# MOSFETS.net
KiCad netlist of a schematic drawn in Altium Designer
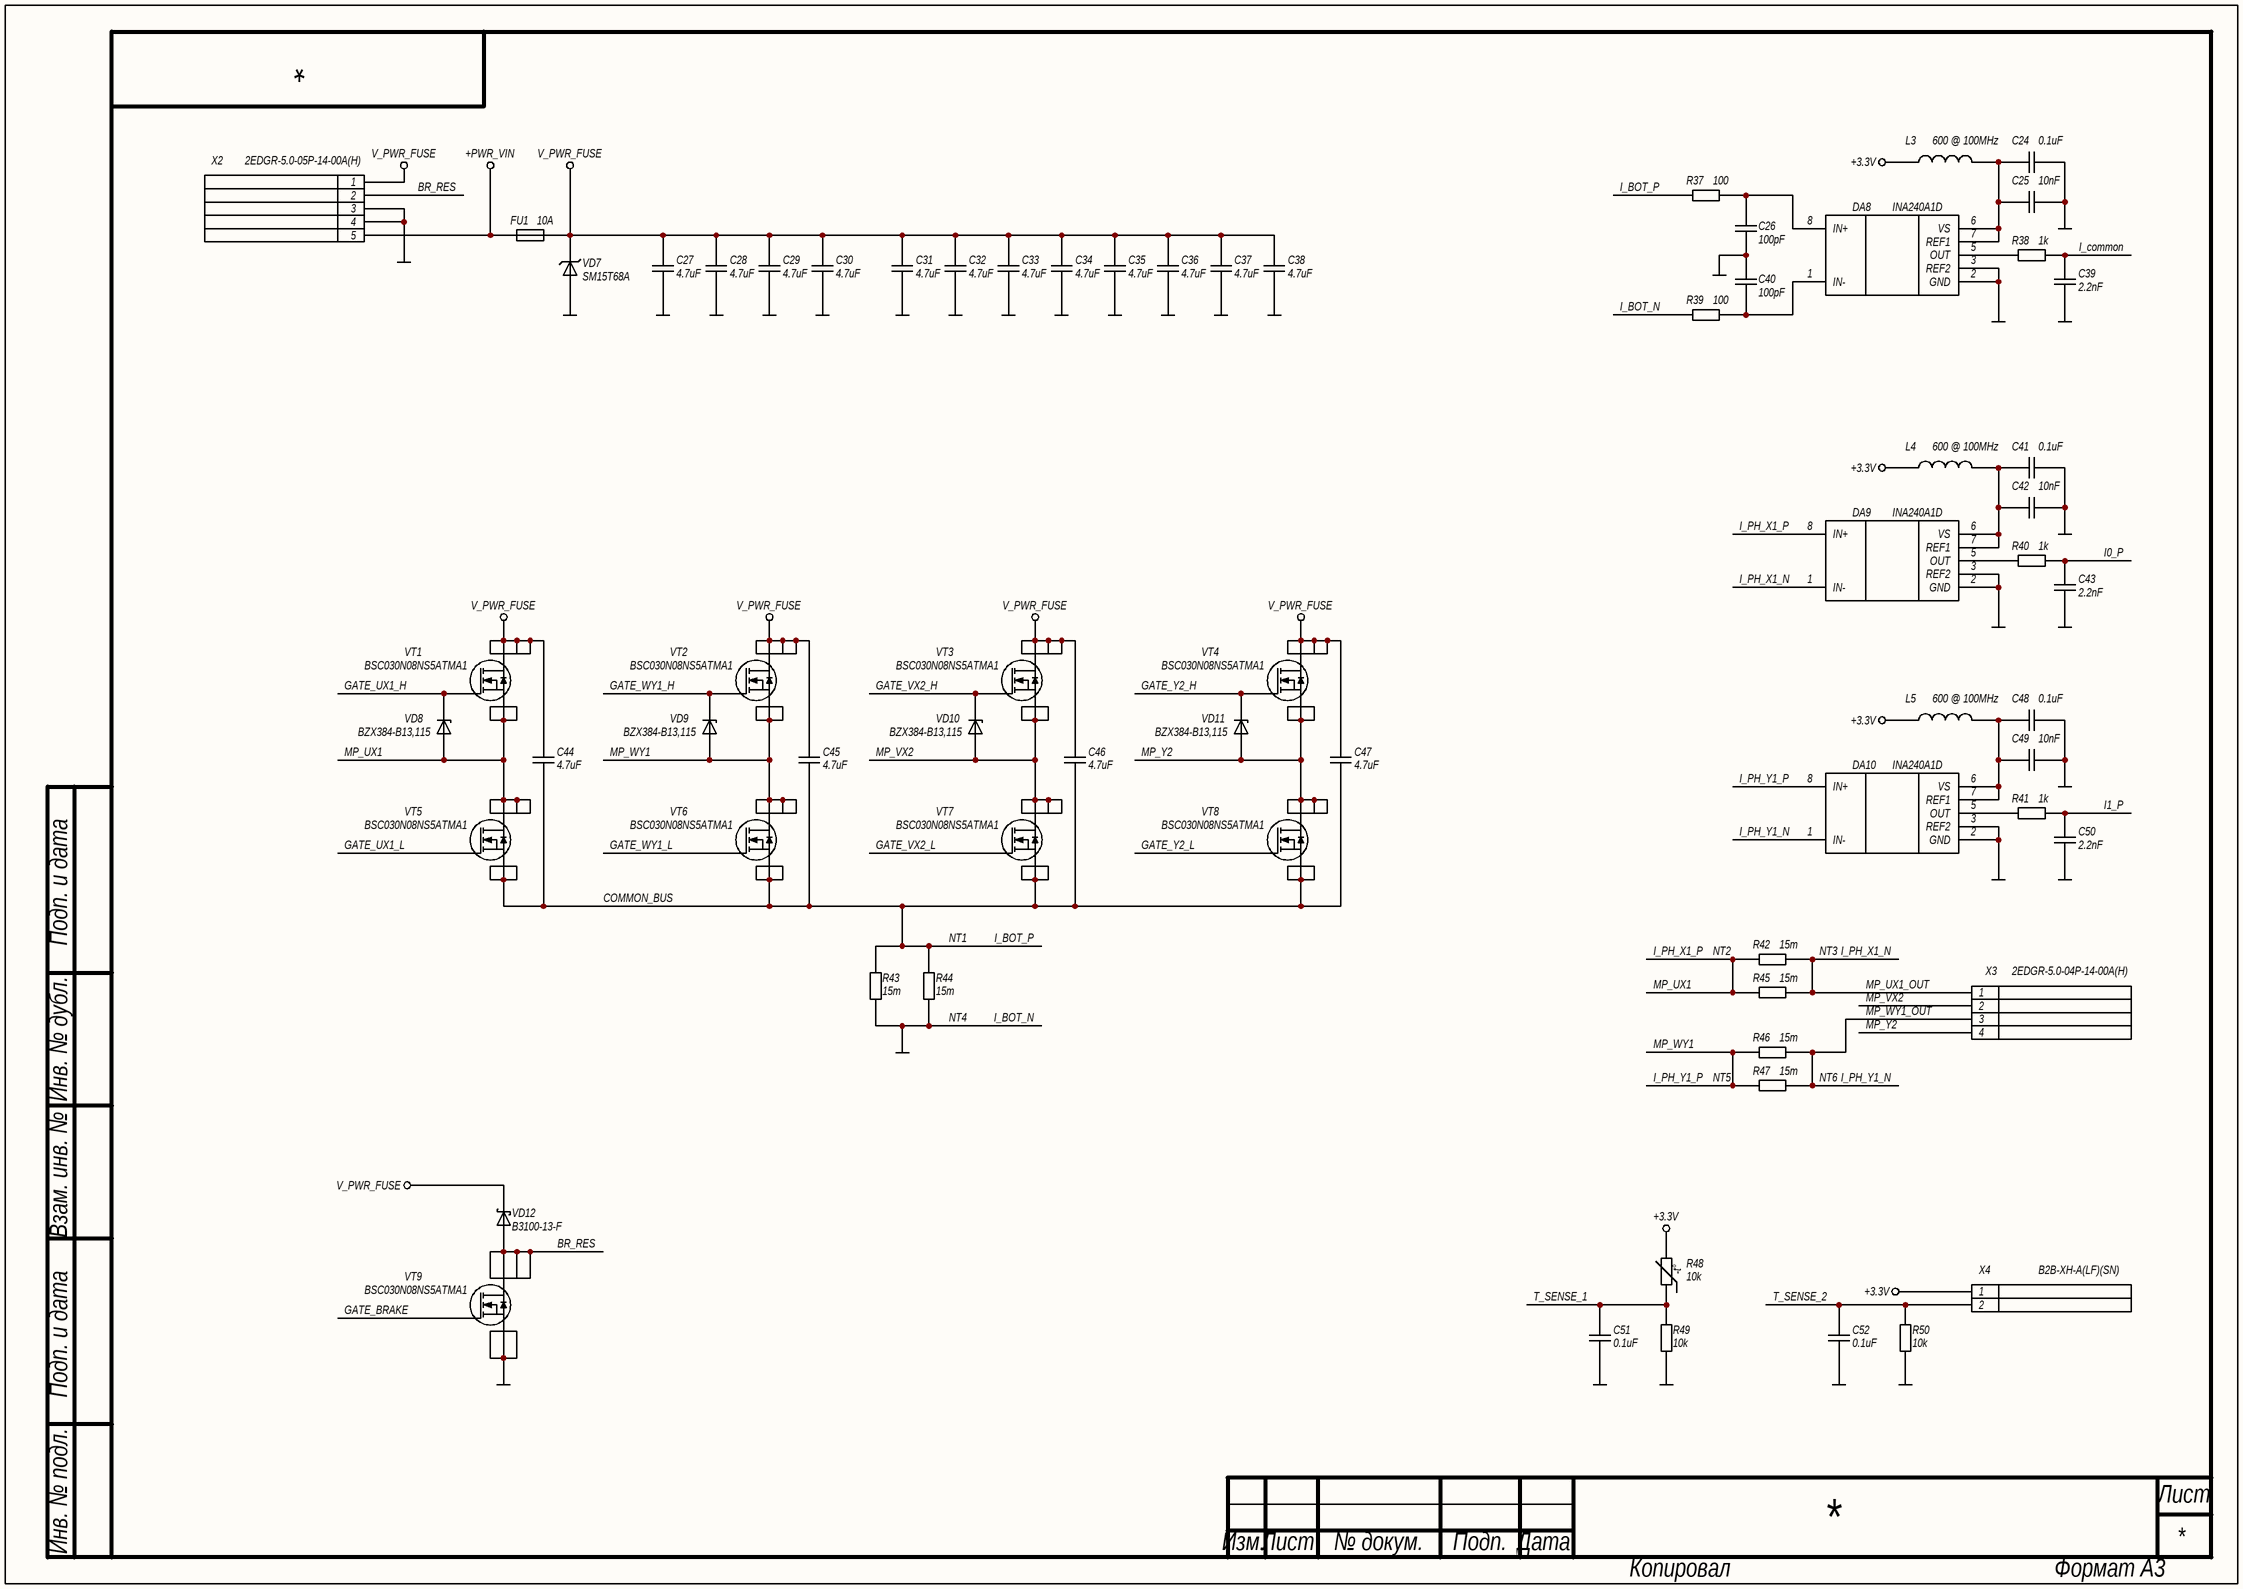
[diagram p0: MOSFETS.SchDoc]

(export (version "E")
  (design (tool "Eeschema 10.0.6"))
  (components
    (comp (ref "C24")
      (value "0.1uF")
      (footprint "C0603N")
      (description "Конденсатор")
      (libsource (lib "Components Library") (part "CAP_FIXED"))
    )
    (comp (ref "C25")
      (value "10nF")
      (footprint "C0603N")
      (description "Конденсатор")
      (libsource (lib "Components Library") (part "CAP_FIXED"))
    )
    (comp (ref "C26")
      (value "100pF")
      (footprint "C0603N")
      (description "Конденсатор")
      (libsource (lib "Components Library") (part "CAP_FIXED"))
    )
    (comp (ref "C27")
      (value "4.7uF")
      (footprint "C1210N")
      (description "Конденсатор")
      (libsource (lib "Components Library") (part "CAP_FIXED"))
    )
    (comp (ref "C28")
      (value "4.7uF")
      (footprint "C1210N")
      (description "Конденсатор")
      (libsource (lib "Components Library") (part "CAP_FIXED"))
    )
    (comp (ref "C29")
      (value "4.7uF")
      (footprint "C1210N")
      (description "Конденсатор")
      (libsource (lib "Components Library") (part "CAP_FIXED"))
    )
    (comp (ref "C30")
      (value "4.7uF")
      (footprint "C1210N")
      (description "Конденсатор")
      (libsource (lib "Components Library") (part "CAP_FIXED"))
    )
    (comp (ref "C31")
      (value "4.7uF")
      (footprint "C1210N")
      (description "Конденсатор")
      (libsource (lib "Components Library") (part "CAP_FIXED"))
    )
    (comp (ref "C32")
      (value "4.7uF")
      (footprint "C1210N")
      (description "Конденсатор")
      (libsource (lib "Components Library") (part "CAP_FIXED"))
    )
    (comp (ref "C33")
      (value "4.7uF")
      (footprint "C1210N")
      (description "Конденсатор")
      (libsource (lib "Components Library") (part "CAP_FIXED"))
    )
    (comp (ref "C34")
      (value "4.7uF")
      (footprint "C1210N")
      (description "Конденсатор")
      (libsource (lib "Components Library") (part "CAP_FIXED"))
    )
    (comp (ref "C35")
      (value "4.7uF")
      (footprint "C1210N")
      (description "Конденсатор")
      (libsource (lib "Components Library") (part "CAP_FIXED"))
    )
    (comp (ref "C36")
      (value "4.7uF")
      (footprint "C1210N")
      (description "Конденсатор")
      (libsource (lib "Components Library") (part "CAP_FIXED"))
    )
    (comp (ref "C37")
      (value "4.7uF")
      (footprint "C1210N")
      (description "Конденсатор")
      (libsource (lib "Components Library") (part "CAP_FIXED"))
    )
    (comp (ref "C38")
      (value "4.7uF")
      (footprint "C1210N")
      (description "Конденсатор")
      (libsource (lib "Components Library") (part "CAP_FIXED"))
    )
    (comp (ref "C39")
      (value "2.2nF")
      (footprint "C0603N")
      (description "Конденсатор")
      (libsource (lib "Components Library") (part "CAP_FIXED"))
    )
    (comp (ref "C40")
      (value "100pF")
      (footprint "C0603N")
      (description "Конденсатор")
      (libsource (lib "Components Library") (part "CAP_FIXED"))
    )
    (comp (ref "C41")
      (value "0.1uF")
      (footprint "C0603N")
      (description "Конденсатор")
      (libsource (lib "Components Library") (part "CAP_FIXED"))
    )
    (comp (ref "C42")
      (value "10nF")
      (footprint "C0603N")
      (description "Конденсатор")
      (libsource (lib "Components Library") (part "CAP_FIXED"))
    )
    (comp (ref "C43")
      (value "2.2nF")
      (footprint "C0603N")
      (description "Конденсатор")
      (libsource (lib "Components Library") (part "CAP_FIXED"))
    )
    (comp (ref "C44")
      (value "4.7uF")
      (footprint "C1210N")
      (description "Конденсатор")
      (libsource (lib "Components Library") (part "CAP_FIXED"))
    )
    (comp (ref "C45")
      (value "4.7uF")
      (footprint "C1210N")
      (description "Конденсатор")
      (libsource (lib "Components Library") (part "CAP_FIXED"))
    )
    (comp (ref "C46")
      (value "4.7uF")
      (footprint "C1210N")
      (description "Конденсатор")
      (libsource (lib "Components Library") (part "CAP_FIXED"))
    )
    (comp (ref "C47")
      (value "4.7uF")
      (footprint "C1210N")
      (description "Конденсатор")
      (libsource (lib "Components Library") (part "CAP_FIXED"))
    )
    (comp (ref "C48")
      (value "0.1uF")
      (footprint "C0603N")
      (description "Конденсатор")
      (libsource (lib "Components Library") (part "CAP_FIXED"))
    )
    (comp (ref "C49")
      (value "10nF")
      (footprint "C0603N")
      (description "Конденсатор")
      (libsource (lib "Components Library") (part "CAP_FIXED"))
    )
    (comp (ref "C50")
      (value "2.2nF")
      (footprint "C0603N")
      (description "Конденсатор")
      (libsource (lib "Components Library") (part "CAP_FIXED"))
    )
    (comp (ref "C51")
      (value "0.1uF")
      (footprint "C0603N")
      (description "Конденсатор")
      (libsource (lib "Components Library") (part "CAP_FIXED"))
    )
    (comp (ref "C52")
      (value "0.1uF")
      (footprint "C0603N")
      (description "Конденсатор")
      (libsource (lib "Components Library") (part "CAP_FIXED"))
    )
    (comp (ref "DA8")
      (value "INA240A1D")
      (footprint "D0008A")
      (description "Микросхема усилитель сигнала токового шунта")
      (libsource (lib "Components Library") (part "INA240AxD"))
    )
    (comp (ref "DA9")
      (value "INA240A1D")
      (footprint "D0008A")
      (description "Микросхема усилитель сигнала токового шунта")
      (libsource (lib "Components Library") (part "INA240AxD"))
    )
    (comp (ref "DA10")
      (value "INA240A1D")
      (footprint "D0008A")
      (description "Микросхема усилитель сигнала токового шунта")
      (libsource (lib "Components Library") (part "INA240AxD"))
    )
    (comp (ref "FU1")
      (value "10A")
      (footprint "0154")
      (description "Плавкий предохранитель")
      (libsource (lib "Components Library") (part "FUSE"))
    )
    (comp (ref "L3")
      (value "600 @ 100MHz")
      (footprint "FB0603N")
      (description "Фильтр ЭМП индуктивный")
      (libsource (lib "Components Library") (part "IND_FILTER"))
    )
    (comp (ref "L4")
      (value "600 @ 100MHz")
      (footprint "FB0603N")
      (description "Фильтр ЭМП индуктивный")
      (libsource (lib "Components Library") (part "IND_FILTER"))
    )
    (comp (ref "L5")
      (value "600 @ 100MHz")
      (footprint "FB0603N")
      (description "Фильтр ЭМП индуктивный")
      (libsource (lib "Components Library") (part "IND_FILTER"))
    )
    (comp (ref "NT1")
      (value "NET_TIE")
      (footprint "NT_0.125_0.375")
      (description "Соединитель цепей (Net Tie)")
      (libsource (lib "Components Library") (part "NET_TIE"))
    )
    (comp (ref "NT2")
      (value "NET_TIE")
      (footprint "NT_0.125_0.375")
      (description "Соединитель цепей (Net Tie)")
      (libsource (lib "Components Library") (part "NET_TIE"))
    )
    (comp (ref "NT3")
      (value "NET_TIE")
      (footprint "NT_0.125_0.375")
      (description "Соединитель цепей (Net Tie)")
      (libsource (lib "Components Library") (part "NET_TIE"))
    )
    (comp (ref "NT4")
      (value "NET_TIE")
      (footprint "NT_0.125_0.375")
      (description "Соединитель цепей (Net Tie)")
      (libsource (lib "Components Library") (part "NET_TIE"))
    )
    (comp (ref "NT5")
      (value "NET_TIE")
      (footprint "NT_0.125_0.375")
      (description "Соединитель цепей (Net Tie)")
      (libsource (lib "Components Library") (part "NET_TIE"))
    )
    (comp (ref "NT6")
      (value "NET_TIE")
      (footprint "NT_0.125_0.375")
      (description "Соединитель цепей (Net Tie)")
      (libsource (lib "Components Library") (part "NET_TIE"))
    )
    (comp (ref "R37")
      (value "100")
      (footprint "R0603N")
      (description "Резистор")
      (libsource (lib "") (part "RES_FIXED_1"))
    )
    (comp (ref "R38")
      (value "1k")
      (footprint "R0603N")
      (description "Резистор")
      (libsource (lib "") (part "RES_FIXED_1"))
    )
    (comp (ref "R39")
      (value "100")
      (footprint "R0603N")
      (description "Резистор")
      (libsource (lib "") (part "RES_FIXED_1"))
    )
    (comp (ref "R40")
      (value "1k")
      (footprint "R0603N")
      (description "Резистор")
      (libsource (lib "") (part "RES_FIXED_1"))
    )
    (comp (ref "R41")
      (value "1k")
      (footprint "R0603N")
      (description "Резистор")
      (libsource (lib "") (part "RES_FIXED_1"))
    )
    (comp (ref "R42")
      (value "15m")
      (footprint "R2512N")
      (description "Резистор")
      (libsource (lib "") (part "RES_FIXED_1"))
    )
    (comp (ref "R43")
      (value "15m")
      (footprint "R2512N")
      (description "Резистор")
      (libsource (lib "Components Library") (part "RES_FIXED"))
    )
    (comp (ref "R44")
      (value "15m")
      (footprint "R2512N")
      (description "Резистор")
      (libsource (lib "Components Library") (part "RES_FIXED"))
    )
    (comp (ref "R45")
      (value "15m")
      (footprint "R2512N")
      (description "Резистор")
      (libsource (lib "") (part "RES_FIXED_1"))
    )
    (comp (ref "R46")
      (value "15m")
      (footprint "R2512N")
      (description "Резистор")
      (libsource (lib "") (part "RES_FIXED_1"))
    )
    (comp (ref "R47")
      (value "15m")
      (footprint "R2512N")
      (description "Резистор")
      (libsource (lib "") (part "RES_FIXED_1"))
    )
    (comp (ref "R48")
      (value "10k")
      (footprint "RT0603N")
      (description "Резистор")
      (libsource (lib "Components Library") (part "RES_NTC"))
    )
    (comp (ref "R49")
      (value "10k")
      (footprint "R0603N")
      (description "Резистор")
      (libsource (lib "Components Library") (part "RES_FIXED"))
    )
    (comp (ref "R50")
      (value "10k")
      (footprint "R0603N")
      (description "Резистор")
      (libsource (lib "Components Library") (part "RES_FIXED"))
    )
    (comp (ref "VD7")
      (value "SM15T68A")
      (footprint "SMC")
      (description "TVS диод однонаправлвенный")
      (libsource (lib "Components Library") (part "TVS_UNIDIR"))
    )
    (comp (ref "VD8")
      (value "BZX384-B13,115")
      (footprint "SOD323")
      (description "Стабилитрон")
      (libsource (lib "Components Library") (part "ZENER"))
    )
    (comp (ref "VD9")
      (value "BZX384-B13,115")
      (footprint "SOD323")
      (description "Стабилитрон")
      (libsource (lib "Components Library") (part "ZENER"))
    )
    (comp (ref "VD10")
      (value "BZX384-B13,115")
      (footprint "SOD323")
      (description "Стабилитрон")
      (libsource (lib "Components Library") (part "ZENER"))
    )
    (comp (ref "VD11")
      (value "BZX384-B13,115")
      (footprint "SOD323")
      (description "Стабилитрон")
      (libsource (lib "Components Library") (part "ZENER"))
    )
    (comp (ref "VD12")
      (value "B3100-13-F")
      (footprint "SMC")
      (description "Диод Шоттки")
      (libsource (lib "Components Library") (part "SCHOTTKY"))
    )
    (comp (ref "VT1")
      (value "BSC030N08NS5ATMA1")
      (footprint "PG-TDSON-8")
      (description "МОП транзистор, N-канальный")
      (libsource (lib "Components Library") (part "N-MOS 8 LEADS_G4"))
    )
    (comp (ref "VT2")
      (value "BSC030N08NS5ATMA1")
      (footprint "PG-TDSON-8")
      (description "МОП транзистор, N-канальный")
      (libsource (lib "Components Library") (part "N-MOS 8 LEADS_G4"))
    )
    (comp (ref "VT3")
      (value "BSC030N08NS5ATMA1")
      (footprint "PG-TDSON-8")
      (description "МОП транзистор, N-канальный")
      (libsource (lib "Components Library") (part "N-MOS 8 LEADS_G4"))
    )
    (comp (ref "VT4")
      (value "BSC030N08NS5ATMA1")
      (footprint "PG-TDSON-8")
      (description "МОП транзистор, N-канальный")
      (libsource (lib "Components Library") (part "N-MOS 8 LEADS_G4"))
    )
    (comp (ref "VT5")
      (value "BSC030N08NS5ATMA1")
      (footprint "PG-TDSON-8")
      (description "МОП транзистор, N-канальный")
      (libsource (lib "Components Library") (part "N-MOS 8 LEADS_G4"))
    )
    (comp (ref "VT6")
      (value "BSC030N08NS5ATMA1")
      (footprint "PG-TDSON-8")
      (description "МОП транзистор, N-канальный")
      (libsource (lib "Components Library") (part "N-MOS 8 LEADS_G4"))
    )
    (comp (ref "VT7")
      (value "BSC030N08NS5ATMA1")
      (footprint "PG-TDSON-8")
      (description "МОП транзистор, N-канальный")
      (libsource (lib "Components Library") (part "N-MOS 8 LEADS_G4"))
    )
    (comp (ref "VT8")
      (value "BSC030N08NS5ATMA1")
      (footprint "PG-TDSON-8")
      (description "МОП транзистор, N-канальный")
      (libsource (lib "Components Library") (part "N-MOS 8 LEADS_G4"))
    )
    (comp (ref "VT9")
      (value "BSC030N08NS5ATMA1")
      (footprint "PG-TDSON-8")
      (description "МОП транзистор, N-канальный")
      (libsource (lib "Components Library") (part "N-MOS 8 LEADS_G4"))
    )
    (comp (ref "X2")
      (value "2EDGR-5.0-05P-14-00A(H)")
      (footprint "2EDGR-5.0-05P-14-00A(H)")
      (description "Разъем, 5 контактов")
      (libsource (lib "Components Library") (part "Connector 5"))
    )
    (comp (ref "X3")
      (value "2EDGR-5.0-04P-14-00A(H)")
      (footprint "2EDGR-5.0-04P-14-00A(H)")
      (description "Разъем, 4 контакта")
      (libsource (lib "Components Library") (part "Connector 4"))
    )
    (comp (ref "X4")
      (value "B2B-XH-A(LF)(SN)")
      (footprint "B2B-XH-A")
      (description "Разъем, 2 контакта")
      (libsource (lib "Components Library") (part "Connector 2"))
    )
  )
  (nets
    (net (code "1") (name "+3.3V") (class "Default")
      (node (ref "L3") (pin "1") (pinfunction "1_1") (pintype "passive"))
      (node (ref "L4") (pin "1") (pinfunction "1_1") (pintype "passive"))
      (node (ref "L5") (pin "1") (pinfunction "1_1") (pintype "passive"))
      (node (ref "R48") (pin "1") (pinfunction "1_1") (pintype "passive"))
      (node (ref "X4") (pin "1") (pinfunction "1_1") (pintype "power_in"))
    )
    (net (code "2") (name "+PWR_VIN") (class "Default")
      (node (ref "FU1") (pin "2") (pinfunction "2_2") (pintype "passive"))
      (node (ref "X2") (pin "5") (pinfunction "5_5") (pintype "power_in"))
    )
    (net (code "3") (name "/BR_RES") (class "Default")
      (node (ref "VD12") (pin "2") (pinfunction "A_2") (pintype "passive"))
      (node (ref "VT9") (pin "5") (pinfunction "D_5") (pintype "passive"))
      (node (ref "VT9") (pin "6") (pinfunction "D_6") (pintype "passive"))
      (node (ref "VT9") (pin "7") (pinfunction "D_7") (pintype "passive"))
      (node (ref "VT9") (pin "8") (pinfunction "D_8") (pintype "passive"))
      (node (ref "X2") (pin "2") (pinfunction "2_2") (pintype "power_in"))
    )
    (net (code "4") (name "/COMMON_BUS") (class "Default")
      (node (ref "C44") (pin "1") (pinfunction "1_1") (pintype "passive"))
      (node (ref "C45") (pin "1") (pinfunction "1_1") (pintype "passive"))
      (node (ref "C46") (pin "1") (pinfunction "1_1") (pintype "passive"))
      (node (ref "C47") (pin "1") (pinfunction "1_1") (pintype "passive"))
      (node (ref "NT1") (pin "2") (pintype "passive"))
      (node (ref "R43") (pin "1") (pinfunction "1_1") (pintype "passive"))
      (node (ref "R44") (pin "1") (pinfunction "1_1") (pintype "passive"))
      (node (ref "VT5") (pin "1") (pinfunction "S_1") (pintype "passive"))
      (node (ref "VT5") (pin "2") (pinfunction "S_2") (pintype "passive"))
      (node (ref "VT5") (pin "3") (pinfunction "S_3") (pintype "passive"))
      (node (ref "VT6") (pin "1") (pinfunction "S_1") (pintype "passive"))
      (node (ref "VT6") (pin "2") (pinfunction "S_2") (pintype "passive"))
      (node (ref "VT6") (pin "3") (pinfunction "S_3") (pintype "passive"))
      (node (ref "VT7") (pin "1") (pinfunction "S_1") (pintype "passive"))
      (node (ref "VT7") (pin "2") (pinfunction "S_2") (pintype "passive"))
      (node (ref "VT7") (pin "3") (pinfunction "S_3") (pintype "passive"))
      (node (ref "VT8") (pin "1") (pinfunction "S_1") (pintype "passive"))
      (node (ref "VT8") (pin "2") (pinfunction "S_2") (pintype "passive"))
      (node (ref "VT8") (pin "3") (pinfunction "S_3") (pintype "passive"))
    )
    (net (code "5") (name "/GATE_BRAKE") (class "Default")
      (node (ref "VT9") (pin "4") (pinfunction "G_4") (pintype "passive"))
    )
    (net (code "6") (name "/GATE_UX1_H") (class "Default")
      (node (ref "VD8") (pin "1") (pinfunction "K_1") (pintype "passive"))
      (node (ref "VT1") (pin "4") (pinfunction "G_4") (pintype "passive"))
    )
    (net (code "7") (name "/GATE_UX1_L") (class "Default")
      (node (ref "VT5") (pin "4") (pinfunction "G_4") (pintype "passive"))
    )
    (net (code "8") (name "/GATE_VX2_H") (class "Default")
      (node (ref "VD10") (pin "1") (pinfunction "K_1") (pintype "passive"))
      (node (ref "VT3") (pin "4") (pinfunction "G_4") (pintype "passive"))
    )
    (net (code "9") (name "/GATE_VX2_L") (class "Default")
      (node (ref "VT7") (pin "4") (pinfunction "G_4") (pintype "passive"))
    )
    (net (code "10") (name "/GATE_WY1_H") (class "Default")
      (node (ref "VD9") (pin "1") (pinfunction "K_1") (pintype "passive"))
      (node (ref "VT2") (pin "4") (pinfunction "G_4") (pintype "passive"))
    )
    (net (code "11") (name "/GATE_WY1_L") (class "Default")
      (node (ref "VT6") (pin "4") (pinfunction "G_4") (pintype "passive"))
    )
    (net (code "12") (name "/GATE_Y2_H") (class "Default")
      (node (ref "VD11") (pin "1") (pinfunction "K_1") (pintype "passive"))
      (node (ref "VT4") (pin "4") (pinfunction "G_4") (pintype "passive"))
    )
    (net (code "13") (name "/GATE_Y2_L") (class "Default")
      (node (ref "VT8") (pin "4") (pinfunction "G_4") (pintype "passive"))
    )
    (net (code "14") (name "/I0_P") (class "Default")
      (node (ref "C43") (pin "2") (pinfunction "2_2") (pintype "passive"))
      (node (ref "R40") (pin "1") (pinfunction "1_1") (pintype "passive"))
    )
    (net (code "15") (name "/I1_P") (class "Default")
      (node (ref "C50") (pin "2") (pinfunction "2_2") (pintype "passive"))
      (node (ref "R41") (pin "1") (pinfunction "1_1") (pintype "passive"))
    )
    (net (code "16") (name "/I_BOT_N") (class "Default")
      (node (ref "NT4") (pin "1") (pintype "passive"))
      (node (ref "R39") (pin "2") (pinfunction "2_2") (pintype "passive"))
    )
    (net (code "17") (name "/I_BOT_P") (class "Default")
      (node (ref "NT1") (pin "1") (pintype "passive"))
      (node (ref "R37") (pin "2") (pinfunction "2_2") (pintype "passive"))
    )
    (net (code "18") (name "/I_PH_X1_N") (class "Default")
      (node (ref "DA9") (pin "1") (pinfunction "IN-_1") (pintype "power_in"))
      (node (ref "NT3") (pin "1") (pintype "passive"))
    )
    (net (code "19") (name "/I_PH_X1_P") (class "Default")
      (node (ref "DA9") (pin "8") (pinfunction "IN+_8") (pintype "power_in"))
      (node (ref "NT2") (pin "2") (pintype "passive"))
    )
    (net (code "20") (name "/I_PH_Y1_N") (class "Default")
      (node (ref "DA10") (pin "1") (pinfunction "IN-_1") (pintype "power_in"))
      (node (ref "NT6") (pin "1") (pintype "passive"))
    )
    (net (code "21") (name "/I_PH_Y1_P") (class "Default")
      (node (ref "DA10") (pin "8") (pinfunction "IN+_8") (pintype "power_in"))
      (node (ref "NT5") (pin "2") (pintype "passive"))
    )
    (net (code "22") (name "/I_common") (class "Default")
      (node (ref "C39") (pin "2") (pinfunction "2_2") (pintype "passive"))
      (node (ref "R38") (pin "1") (pinfunction "1_1") (pintype "passive"))
    )
    (net (code "23") (name "/MP_UX1") (class "Default")
      (node (ref "NT2") (pin "1") (pintype "passive"))
      (node (ref "R42") (pin "2") (pinfunction "2_2") (pintype "passive"))
      (node (ref "R45") (pin "2") (pinfunction "2_2") (pintype "passive"))
      (node (ref "VD8") (pin "2") (pinfunction "A_2") (pintype "passive"))
      (node (ref "VT1") (pin "1") (pinfunction "S_1") (pintype "passive"))
      (node (ref "VT1") (pin "2") (pinfunction "S_2") (pintype "passive"))
      (node (ref "VT1") (pin "3") (pinfunction "S_3") (pintype "passive"))
      (node (ref "VT5") (pin "5") (pinfunction "D_5") (pintype "passive"))
      (node (ref "VT5") (pin "6") (pinfunction "D_6") (pintype "passive"))
      (node (ref "VT5") (pin "7") (pinfunction "D_7") (pintype "passive"))
      (node (ref "VT5") (pin "8") (pinfunction "D_8") (pintype "passive"))
    )
    (net (code "24") (name "/MP_UX1_OUT") (class "Default")
      (node (ref "NT3") (pin "2") (pintype "passive"))
      (node (ref "R42") (pin "1") (pinfunction "1_1") (pintype "passive"))
      (node (ref "R45") (pin "1") (pinfunction "1_1") (pintype "passive"))
      (node (ref "X3") (pin "1") (pinfunction "1_1") (pintype "power_in"))
    )
    (net (code "25") (name "/MP_VX2") (class "Default")
      (node (ref "VD10") (pin "2") (pinfunction "A_2") (pintype "passive"))
      (node (ref "VT3") (pin "1") (pinfunction "S_1") (pintype "passive"))
      (node (ref "VT3") (pin "2") (pinfunction "S_2") (pintype "passive"))
      (node (ref "VT3") (pin "3") (pinfunction "S_3") (pintype "passive"))
      (node (ref "VT7") (pin "5") (pinfunction "D_5") (pintype "passive"))
      (node (ref "VT7") (pin "6") (pinfunction "D_6") (pintype "passive"))
      (node (ref "VT7") (pin "7") (pinfunction "D_7") (pintype "passive"))
      (node (ref "VT7") (pin "8") (pinfunction "D_8") (pintype "passive"))
      (node (ref "X3") (pin "2") (pinfunction "2_2") (pintype "power_in"))
    )
    (net (code "26") (name "/MP_WY1") (class "Default")
      (node (ref "NT5") (pin "1") (pintype "passive"))
      (node (ref "R46") (pin "2") (pinfunction "2_2") (pintype "passive"))
      (node (ref "R47") (pin "2") (pinfunction "2_2") (pintype "passive"))
      (node (ref "VD9") (pin "2") (pinfunction "A_2") (pintype "passive"))
      (node (ref "VT2") (pin "1") (pinfunction "S_1") (pintype "passive"))
      (node (ref "VT2") (pin "2") (pinfunction "S_2") (pintype "passive"))
      (node (ref "VT2") (pin "3") (pinfunction "S_3") (pintype "passive"))
      (node (ref "VT6") (pin "5") (pinfunction "D_5") (pintype "passive"))
      (node (ref "VT6") (pin "6") (pinfunction "D_6") (pintype "passive"))
      (node (ref "VT6") (pin "7") (pinfunction "D_7") (pintype "passive"))
      (node (ref "VT6") (pin "8") (pinfunction "D_8") (pintype "passive"))
    )
    (net (code "27") (name "/MP_WY1_OUT") (class "Default")
      (node (ref "NT6") (pin "2") (pintype "passive"))
      (node (ref "R46") (pin "1") (pinfunction "1_1") (pintype "passive"))
      (node (ref "R47") (pin "1") (pinfunction "1_1") (pintype "passive"))
      (node (ref "X3") (pin "3") (pinfunction "3_3") (pintype "power_in"))
    )
    (net (code "28") (name "/MP_Y2") (class "Default")
      (node (ref "VD11") (pin "2") (pinfunction "A_2") (pintype "passive"))
      (node (ref "VT4") (pin "1") (pinfunction "S_1") (pintype "passive"))
      (node (ref "VT4") (pin "2") (pinfunction "S_2") (pintype "passive"))
      (node (ref "VT4") (pin "3") (pinfunction "S_3") (pintype "passive"))
      (node (ref "VT8") (pin "5") (pinfunction "D_5") (pintype "passive"))
      (node (ref "VT8") (pin "6") (pinfunction "D_6") (pintype "passive"))
      (node (ref "VT8") (pin "7") (pinfunction "D_7") (pintype "passive"))
      (node (ref "VT8") (pin "8") (pinfunction "D_8") (pintype "passive"))
      (node (ref "X3") (pin "4") (pinfunction "4_4") (pintype "power_in"))
    )
    (net (code "29") (name "/T_SENSE_1") (class "Default")
      (node (ref "C51") (pin "1") (pinfunction "1_1") (pintype "passive"))
      (node (ref "R48") (pin "2") (pinfunction "2_2") (pintype "passive"))
      (node (ref "R49") (pin "1") (pinfunction "1_1") (pintype "passive"))
    )
    (net (code "30") (name "/T_SENSE_2") (class "Default")
      (node (ref "C52") (pin "1") (pinfunction "1_1") (pintype "passive"))
      (node (ref "R50") (pin "1") (pinfunction "1_1") (pintype "passive"))
      (node (ref "X4") (pin "2") (pinfunction "2_2") (pintype "power_in"))
    )
    (net (code "31") (name "GND") (class "Default")
      (node (ref "C24") (pin "1") (pinfunction "1_1") (pintype "passive"))
      (node (ref "C25") (pin "1") (pinfunction "1_1") (pintype "passive"))
      (node (ref "C26") (pin "2") (pinfunction "2_2") (pintype "passive"))
      (node (ref "C27") (pin "1") (pinfunction "1_1") (pintype "passive"))
      (node (ref "C28") (pin "1") (pinfunction "1_1") (pintype "passive"))
      (node (ref "C29") (pin "1") (pinfunction "1_1") (pintype "passive"))
      (node (ref "C30") (pin "1") (pinfunction "1_1") (pintype "passive"))
      (node (ref "C31") (pin "1") (pinfunction "1_1") (pintype "passive"))
      (node (ref "C32") (pin "1") (pinfunction "1_1") (pintype "passive"))
      (node (ref "C33") (pin "1") (pinfunction "1_1") (pintype "passive"))
      (node (ref "C34") (pin "1") (pinfunction "1_1") (pintype "passive"))
      (node (ref "C35") (pin "1") (pinfunction "1_1") (pintype "passive"))
      (node (ref "C36") (pin "1") (pinfunction "1_1") (pintype "passive"))
      (node (ref "C37") (pin "1") (pinfunction "1_1") (pintype "passive"))
      (node (ref "C38") (pin "1") (pinfunction "1_1") (pintype "passive"))
      (node (ref "C39") (pin "1") (pinfunction "1_1") (pintype "passive"))
      (node (ref "C40") (pin "1") (pinfunction "1_1") (pintype "passive"))
      (node (ref "C41") (pin "1") (pinfunction "1_1") (pintype "passive"))
      (node (ref "C42") (pin "1") (pinfunction "1_1") (pintype "passive"))
      (node (ref "C43") (pin "1") (pinfunction "1_1") (pintype "passive"))
      (node (ref "C48") (pin "1") (pinfunction "1_1") (pintype "passive"))
      (node (ref "C49") (pin "1") (pinfunction "1_1") (pintype "passive"))
      (node (ref "C50") (pin "1") (pinfunction "1_1") (pintype "passive"))
      (node (ref "C51") (pin "2") (pinfunction "2_2") (pintype "passive"))
      (node (ref "C52") (pin "2") (pinfunction "2_2") (pintype "passive"))
      (node (ref "DA10") (pin "2") (pinfunction "GND_2") (pintype "power_in"))
      (node (ref "DA10") (pin "3") (pinfunction "REF2_3") (pintype "power_in"))
      (node (ref "DA8") (pin "2") (pinfunction "GND_2") (pintype "power_in"))
      (node (ref "DA8") (pin "3") (pinfunction "REF2_3") (pintype "power_in"))
      (node (ref "DA9") (pin "2") (pinfunction "GND_2") (pintype "power_in"))
      (node (ref "DA9") (pin "3") (pinfunction "REF2_3") (pintype "power_in"))
      (node (ref "NT4") (pin "2") (pintype "passive"))
      (node (ref "R43") (pin "2") (pinfunction "2_2") (pintype "passive"))
      (node (ref "R44") (pin "2") (pinfunction "2_2") (pintype "passive"))
      (node (ref "R49") (pin "2") (pinfunction "2_2") (pintype "passive"))
      (node (ref "R50") (pin "2") (pinfunction "2_2") (pintype "passive"))
      (node (ref "VD7") (pin "2") (pinfunction "A_2") (pintype "passive"))
      (node (ref "VT9") (pin "1") (pinfunction "S_1") (pintype "passive"))
      (node (ref "VT9") (pin "2") (pinfunction "S_2") (pintype "passive"))
      (node (ref "VT9") (pin "3") (pinfunction "S_3") (pintype "passive"))
      (node (ref "X2") (pin "3") (pinfunction "3_3") (pintype "power_in"))
      (node (ref "X2") (pin "4") (pinfunction "4_4") (pintype "power_in"))
    )
    (net (code "32") (name "Net-(DA8-IN+)") (class "Default")
      (node (ref "C26") (pin "1") (pinfunction "1_1") (pintype "passive"))
      (node (ref "DA8") (pin "8") (pinfunction "IN+_8") (pintype "power_in"))
      (node (ref "R37") (pin "1") (pinfunction "1_1") (pintype "passive"))
    )
    (net (code "33") (name "Net-(DA8-IN-)") (class "Default")
      (node (ref "C40") (pin "2") (pinfunction "2_2") (pintype "passive"))
      (node (ref "DA8") (pin "1") (pinfunction "IN-_1") (pintype "power_in"))
      (node (ref "R39") (pin "1") (pinfunction "1_1") (pintype "passive"))
    )
    (net (code "34") (name "Net-(DA8-OUT)") (class "Default")
      (node (ref "DA8") (pin "5") (pinfunction "OUT_5") (pintype "power_in"))
      (node (ref "R38") (pin "2") (pinfunction "2_2") (pintype "passive"))
    )
    (net (code "35") (name "Net-(DA8-REF1)") (class "Default")
      (node (ref "C24") (pin "2") (pinfunction "2_2") (pintype "passive"))
      (node (ref "C25") (pin "2") (pinfunction "2_2") (pintype "passive"))
      (node (ref "DA8") (pin "6") (pinfunction "VS_6") (pintype "power_in"))
      (node (ref "DA8") (pin "7") (pinfunction "REF1_7") (pintype "power_in"))
      (node (ref "L3") (pin "2") (pinfunction "2_2") (pintype "passive"))
    )
    (net (code "36") (name "Net-(DA9-OUT)") (class "Default")
      (node (ref "DA9") (pin "5") (pinfunction "OUT_5") (pintype "power_in"))
      (node (ref "R40") (pin "2") (pinfunction "2_2") (pintype "passive"))
    )
    (net (code "37") (name "Net-(DA9-REF1)") (class "Default")
      (node (ref "C41") (pin "2") (pinfunction "2_2") (pintype "passive"))
      (node (ref "C42") (pin "2") (pinfunction "2_2") (pintype "passive"))
      (node (ref "DA9") (pin "6") (pinfunction "VS_6") (pintype "power_in"))
      (node (ref "DA9") (pin "7") (pinfunction "REF1_7") (pintype "power_in"))
      (node (ref "L4") (pin "2") (pinfunction "2_2") (pintype "passive"))
    )
    (net (code "38") (name "Net-(DA10-OUT)") (class "Default")
      (node (ref "DA10") (pin "5") (pinfunction "OUT_5") (pintype "power_in"))
      (node (ref "R41") (pin "2") (pinfunction "2_2") (pintype "passive"))
    )
    (net (code "39") (name "Net-(DA10-REF1)") (class "Default")
      (node (ref "C48") (pin "2") (pinfunction "2_2") (pintype "passive"))
      (node (ref "C49") (pin "2") (pinfunction "2_2") (pintype "passive"))
      (node (ref "DA10") (pin "6") (pinfunction "VS_6") (pintype "power_in"))
      (node (ref "DA10") (pin "7") (pinfunction "REF1_7") (pintype "power_in"))
      (node (ref "L5") (pin "2") (pinfunction "2_2") (pintype "passive"))
    )
    (net (code "40") (name "V_PWR_FUSE") (class "Default")
      (node (ref "C27") (pin "2") (pinfunction "2_2") (pintype "passive"))
      (node (ref "C28") (pin "2") (pinfunction "2_2") (pintype "passive"))
      (node (ref "C29") (pin "2") (pinfunction "2_2") (pintype "passive"))
      (node (ref "C30") (pin "2") (pinfunction "2_2") (pintype "passive"))
      (node (ref "C31") (pin "2") (pinfunction "2_2") (pintype "passive"))
      (node (ref "C32") (pin "2") (pinfunction "2_2") (pintype "passive"))
      (node (ref "C33") (pin "2") (pinfunction "2_2") (pintype "passive"))
      (node (ref "C34") (pin "2") (pinfunction "2_2") (pintype "passive"))
      (node (ref "C35") (pin "2") (pinfunction "2_2") (pintype "passive"))
      (node (ref "C36") (pin "2") (pinfunction "2_2") (pintype "passive"))
      (node (ref "C37") (pin "2") (pinfunction "2_2") (pintype "passive"))
      (node (ref "C38") (pin "2") (pinfunction "2_2") (pintype "passive"))
      (node (ref "C44") (pin "2") (pinfunction "2_2") (pintype "passive"))
      (node (ref "C45") (pin "2") (pinfunction "2_2") (pintype "passive"))
      (node (ref "C46") (pin "2") (pinfunction "2_2") (pintype "passive"))
      (node (ref "C47") (pin "2") (pinfunction "2_2") (pintype "passive"))
      (node (ref "FU1") (pin "1") (pinfunction "1_1") (pintype "passive"))
      (node (ref "VD12") (pin "1") (pinfunction "K_1") (pintype "passive"))
      (node (ref "VD7") (pin "1") (pinfunction "K_1") (pintype "passive"))
      (node (ref "VT1") (pin "5") (pinfunction "D_5") (pintype "passive"))
      (node (ref "VT1") (pin "6") (pinfunction "D_6") (pintype "passive"))
      (node (ref "VT1") (pin "7") (pinfunction "D_7") (pintype "passive"))
      (node (ref "VT1") (pin "8") (pinfunction "D_8") (pintype "passive"))
      (node (ref "VT2") (pin "5") (pinfunction "D_5") (pintype "passive"))
      (node (ref "VT2") (pin "6") (pinfunction "D_6") (pintype "passive"))
      (node (ref "VT2") (pin "7") (pinfunction "D_7") (pintype "passive"))
      (node (ref "VT2") (pin "8") (pinfunction "D_8") (pintype "passive"))
      (node (ref "VT3") (pin "5") (pinfunction "D_5") (pintype "passive"))
      (node (ref "VT3") (pin "6") (pinfunction "D_6") (pintype "passive"))
      (node (ref "VT3") (pin "7") (pinfunction "D_7") (pintype "passive"))
      (node (ref "VT3") (pin "8") (pinfunction "D_8") (pintype "passive"))
      (node (ref "VT4") (pin "5") (pinfunction "D_5") (pintype "passive"))
      (node (ref "VT4") (pin "6") (pinfunction "D_6") (pintype "passive"))
      (node (ref "VT4") (pin "7") (pinfunction "D_7") (pintype "passive"))
      (node (ref "VT4") (pin "8") (pinfunction "D_8") (pintype "passive"))
      (node (ref "X2") (pin "1") (pinfunction "1_1") (pintype "power_in"))
    )
  )
)
